# 04C-003.net
KiCad netlist of a schematic drawn in EAGLE
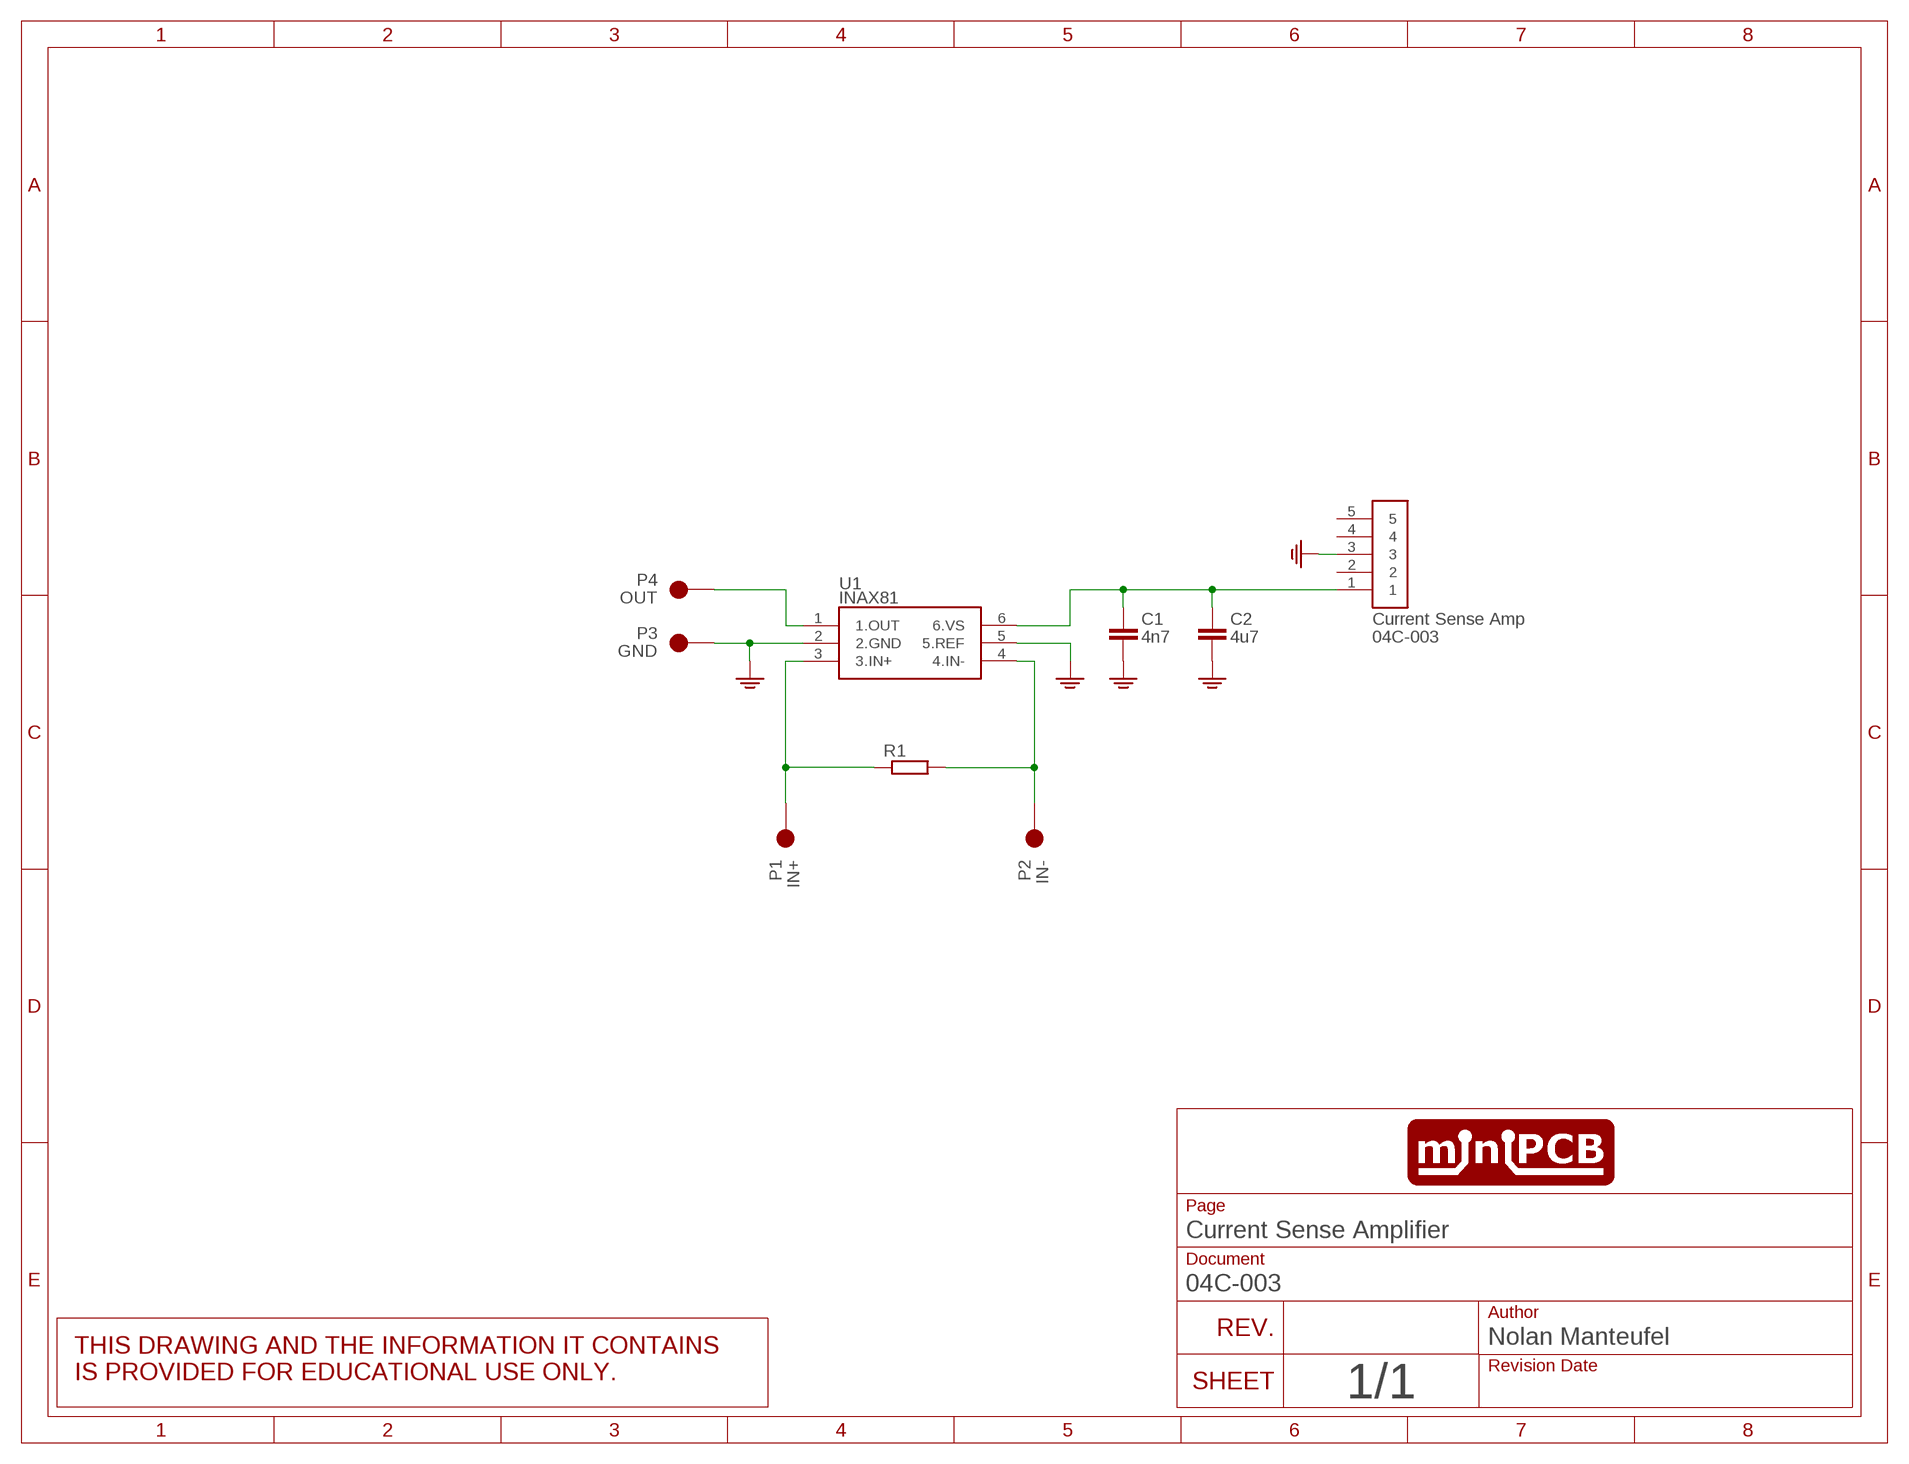
[diagram p0: schematic, sheet 1]

(export (version "E")
  (design (tool "Eeschema 10.0.6"))
  (components
    (comp (ref "04C-003")
      (value "Current Sense Amp")
      (footprint "eagle-import:MINIPCB_25X25MM")
      (libsource (lib "eagle-import") (part "MINIPCB_5P25MM"))
    )
    (comp (ref "C1")
      (value "4n7")
      (footprint "eagle-import:C0603")
      (libsource (lib "eagle-import") (part "C-EUC0603"))
    )
    (comp (ref "C2")
      (value "4u7")
      (footprint "eagle-import:C0603")
      (libsource (lib "eagle-import") (part "C-EUC0603"))
    )
    (comp (ref "P1")
      (value "IN+")
      (footprint "eagle-import:PINS_1_1MM_K")
      (libsource (lib "eagle-import") (part "PINS_124AWG-K"))
    )
    (comp (ref "P2")
      (value "IN-")
      (footprint "eagle-import:PINS_1_1MM_K")
      (libsource (lib "eagle-import") (part "PINS_124AWG-K"))
    )
    (comp (ref "P3")
      (value "GND")
      (footprint "eagle-import:PINS_1_1MM_K")
      (libsource (lib "eagle-import") (part "PINS_124AWG-K"))
    )
    (comp (ref "P4")
      (value "OUT")
      (footprint "eagle-import:PINS_1_1MM_K")
      (libsource (lib "eagle-import") (part "PINS_124AWG-K"))
    )
    (comp (ref "R1")
      (value "R-EU_R2512K")
      (footprint "eagle-import:R2512K")
      (libsource (lib "eagle-import") (part "R-EU_R2512K"))
    )
    (comp (ref "U1")
      (value "INAX81")
      (footprint "eagle-import:SOT23-6")
      (libsource (lib "eagle-import") (part "INAX81"))
    )
  )
  (nets
    (net (code "1") (name "GND") (class "Default")
      (node (ref "04C-003") (pin "3") (pinfunction "3_3") (pintype "bidirectional"))
      (node (ref "C1") (pin "2") (pinfunction "2_2") (pintype "passive"))
      (node (ref "C2") (pin "2") (pinfunction "2_2") (pintype "passive"))
      (node (ref "P3") (pin "1") (pinfunction "1_1") (pintype "bidirectional"))
      (node (ref "P3") (pin "2") (pinfunction "1_2") (pintype "bidirectional"))
      (node (ref "U1") (pin "2") (pinfunction "2.GND_2") (pintype "bidirectional"))
      (node (ref "U1") (pin "5") (pinfunction "5.REF_5") (pintype "bidirectional"))
    )
    (net (code "2") (name "Net-(U1-1.OUT)") (class "Default")
      (node (ref "P4") (pin "1") (pinfunction "1_1") (pintype "bidirectional"))
      (node (ref "P4") (pin "2") (pinfunction "1_2") (pintype "bidirectional"))
      (node (ref "U1") (pin "1") (pinfunction "1.OUT_1") (pintype "bidirectional"))
    )
    (net (code "3") (name "Net-(U1-3.IN+)") (class "Default")
      (node (ref "P1") (pin "1") (pinfunction "1_1") (pintype "bidirectional"))
      (node (ref "P1") (pin "2") (pinfunction "1_2") (pintype "bidirectional"))
      (node (ref "R1") (pin "1") (pinfunction "1_1") (pintype "passive"))
      (node (ref "U1") (pin "3") (pinfunction "3.IN+_3") (pintype "bidirectional"))
    )
    (net (code "4") (name "Net-(U1-4.IN-)") (class "Default")
      (node (ref "P2") (pin "1") (pinfunction "1_1") (pintype "bidirectional"))
      (node (ref "P2") (pin "2") (pinfunction "1_2") (pintype "bidirectional"))
      (node (ref "R1") (pin "2") (pinfunction "2_2") (pintype "passive"))
      (node (ref "U1") (pin "4") (pinfunction "4.IN-_4") (pintype "bidirectional"))
    )
    (net (code "5") (name "Net-(U1-6.VS)") (class "Default")
      (node (ref "04C-003") (pin "1") (pinfunction "1_1") (pintype "bidirectional"))
      (node (ref "C1") (pin "1") (pinfunction "1_1") (pintype "passive"))
      (node (ref "C2") (pin "1") (pinfunction "1_1") (pintype "passive"))
      (node (ref "U1") (pin "6") (pinfunction "6.VS_6") (pintype "bidirectional"))
    )
    (net (code "6") (name "unconnected-(04C-003-Pad2)") (class "Default")
      (node (ref "04C-003") (pin "2") (pinfunction "2_2") (pintype "bidirectional"))
    )
    (net (code "7") (name "unconnected-(04C-003-Pad4)") (class "Default")
      (node (ref "04C-003") (pin "4") (pinfunction "4_4") (pintype "bidirectional"))
    )
    (net (code "8") (name "unconnected-(04C-003-Pad5)") (class "Default")
      (node (ref "04C-003") (pin "5") (pinfunction "5_5") (pintype "bidirectional"))
    )
  )
)
